# 1-Schematic_Logic.net
KiCad netlist of a schematic drawn in EasyEDA
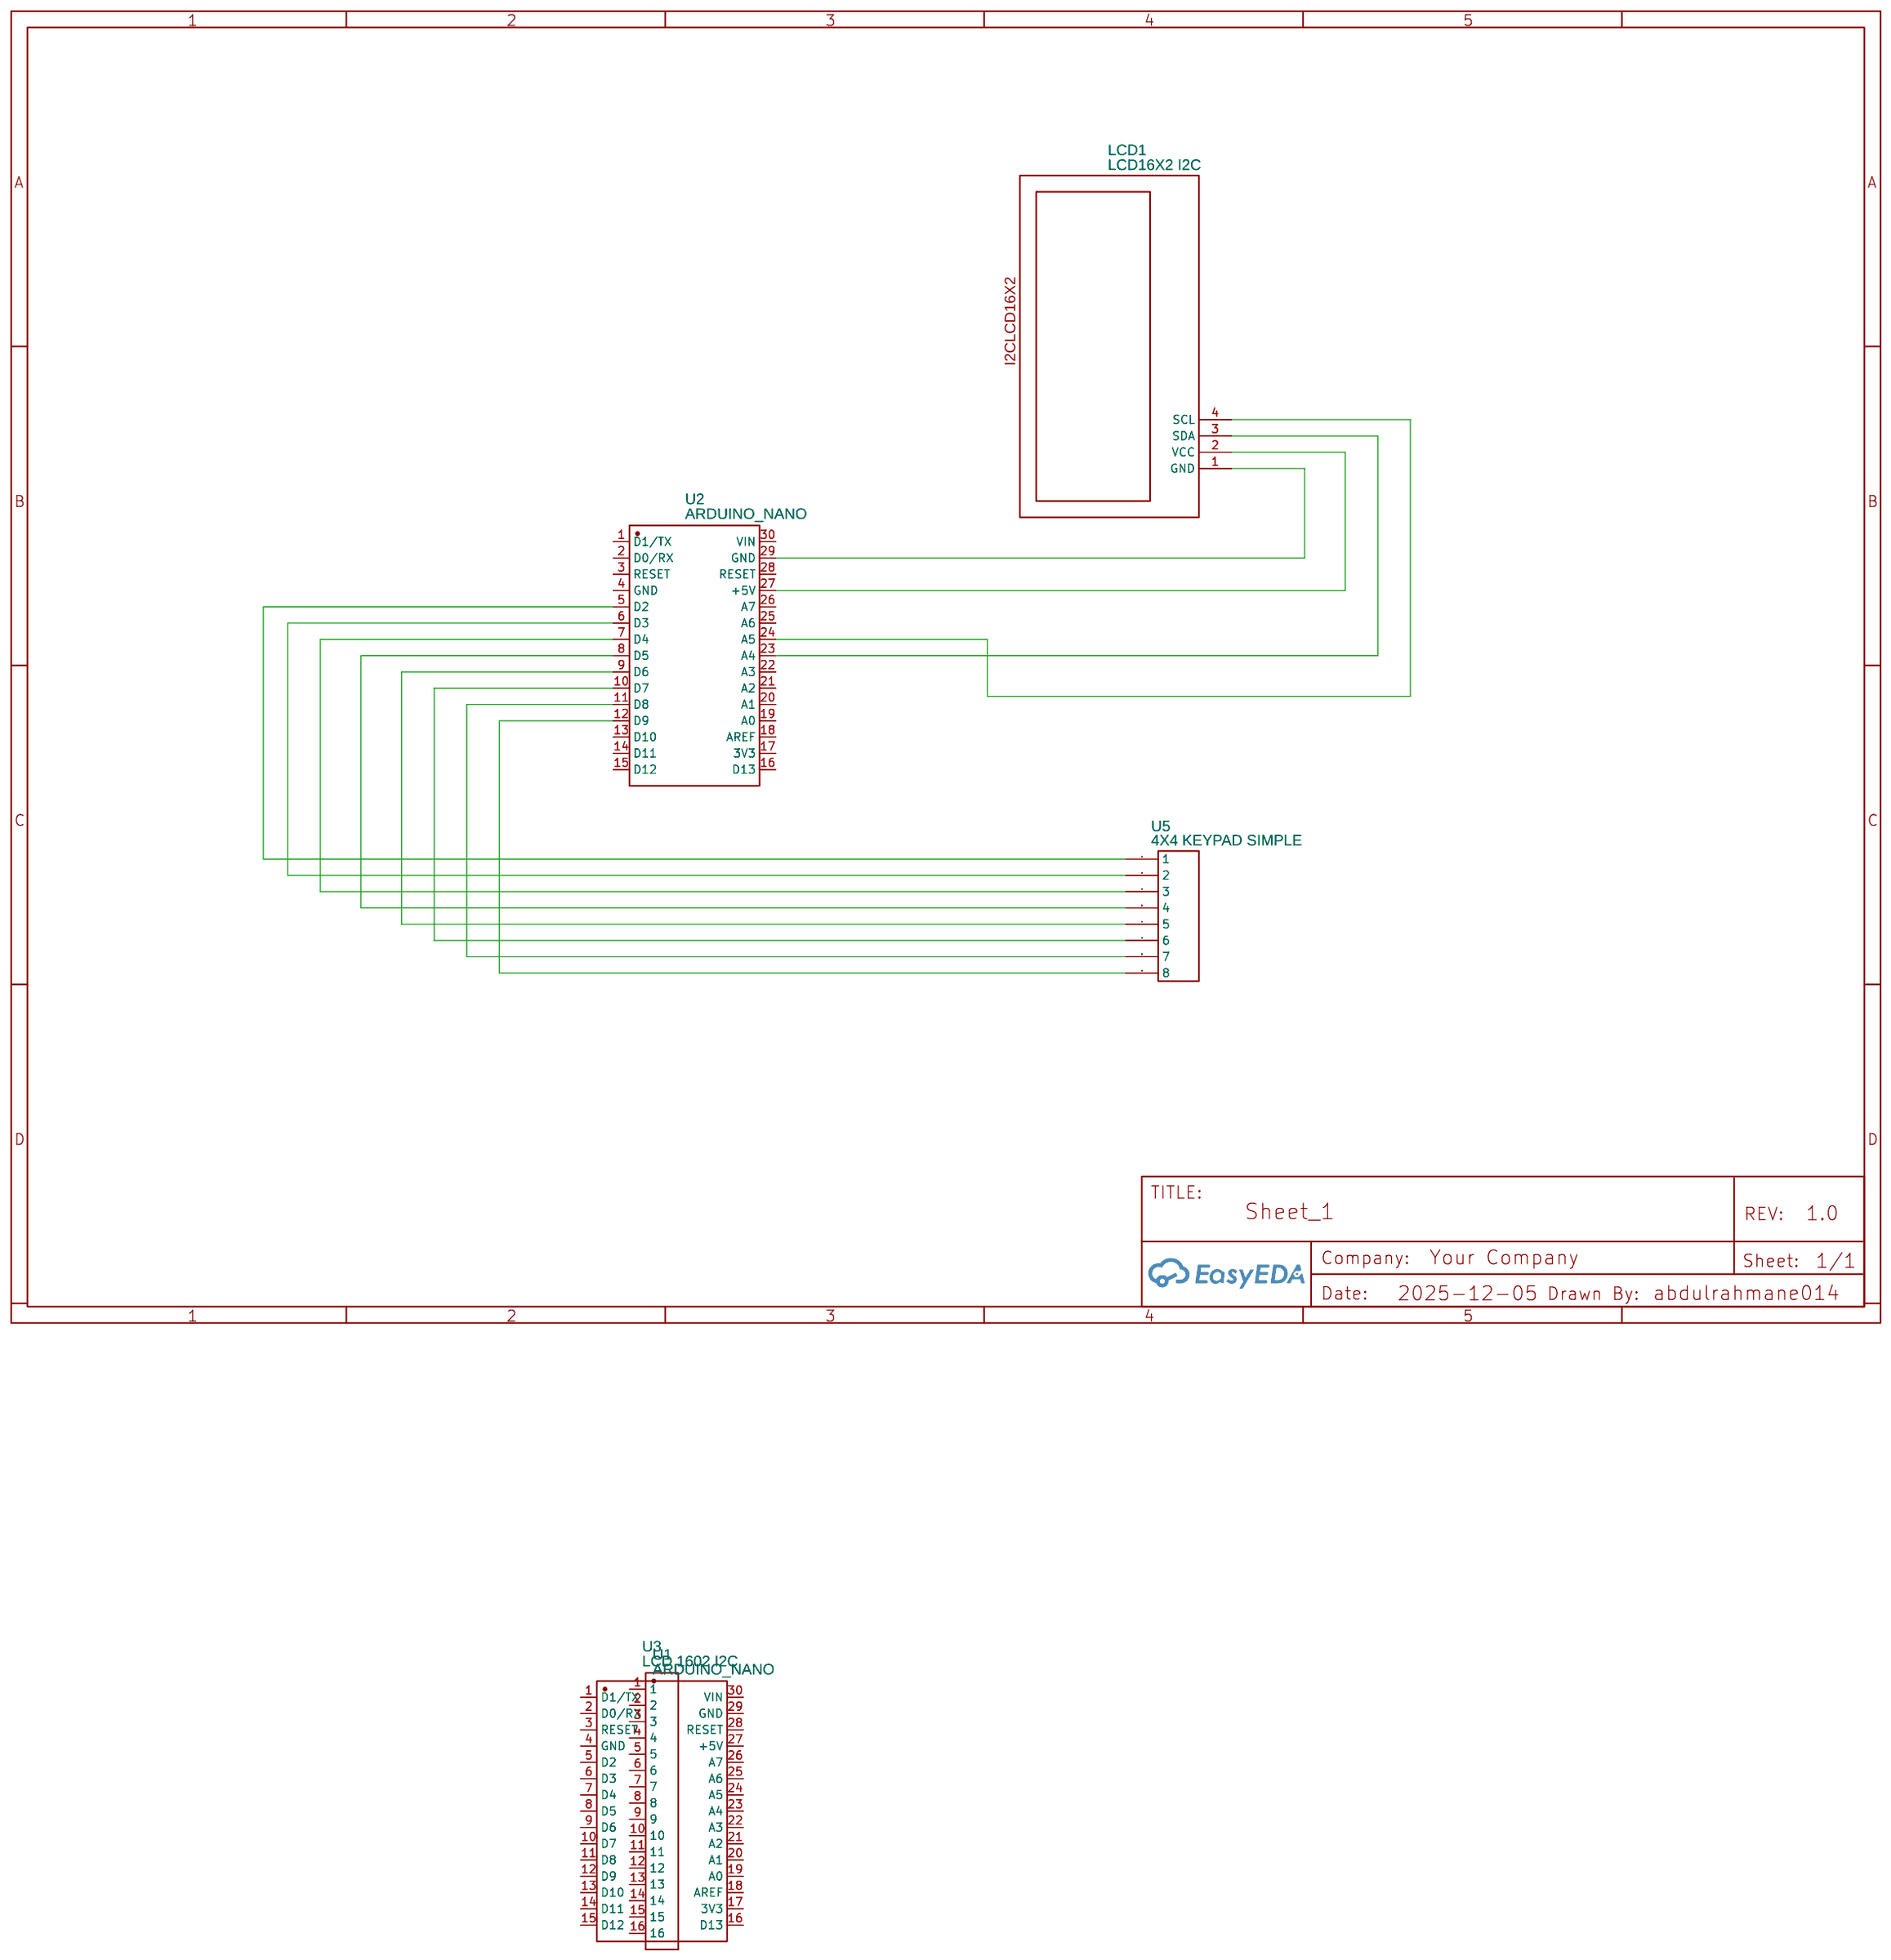
[diagram p0: schematic sheet]

(export (version "E")
  (design (tool "Eeschema 10.0.6"))
  (components
    (comp (ref "LCD1") (value "LCD16X2 I2C") (libsource (lib "") (part "LCD16X2 I2C")))
    (comp (ref "U1") (value "ARDUINO_NANO") (libsource (lib "") (part "ARDUINO_NANO")))
    (comp (ref "U2") (value "ARDUINO_NANO") (libsource (lib "") (part "ARDUINO_NANO")))
    (comp (ref "U3") (value "LCD 1602 I2C") (libsource (lib "") (part "LCD 1602 I2C")))
    (comp (ref "U5") (value "4X4 KEYPAD SIMPLE") (libsource (lib "") (part "4X4 KEYPAD SIMPLE")))
  )
  (nets
    (net (code "1") (name "Net-(LCD1-GND)") (class "Default")
      (node (ref "LCD1") (pin "1") (pinfunction "GND_1") (pintype "unspecified"))
      (node (ref "U2") (pin "29") (pinfunction "GND_29") (pintype "unspecified"))
    )
    (net (code "2") (name "Net-(LCD1-SCL)") (class "Default")
      (node (ref "LCD1") (pin "4") (pinfunction "SCL_4") (pintype "unspecified"))
      (node (ref "U2") (pin "24") (pinfunction "A5_24") (pintype "unspecified"))
    )
    (net (code "3") (name "Net-(LCD1-SDA)") (class "Default")
      (node (ref "LCD1") (pin "3") (pinfunction "SDA_3") (pintype "unspecified"))
      (node (ref "U2") (pin "23") (pinfunction "A4_23") (pintype "unspecified"))
    )
    (net (code "4") (name "Net-(LCD1-VCC)") (class "Default")
      (node (ref "LCD1") (pin "2") (pinfunction "VCC_2") (pintype "unspecified"))
      (node (ref "U2") (pin "27") (pinfunction "+5V_27") (pintype "unspecified"))
    )
    (net (code "5") (name "Net-(U2-D2)") (class "Default")
      (node (ref "U2") (pin "5") (pinfunction "D2_5") (pintype "unspecified"))
      (node (ref "U5") (pin "3") (pinfunction "1_3") (pintype "unspecified"))
    )
    (net (code "6") (name "Net-(U2-D3)") (class "Default")
      (node (ref "U2") (pin "6") (pinfunction "D3_6") (pintype "unspecified"))
      (node (ref "U5") (pin "4") (pinfunction "2_4") (pintype "unspecified"))
    )
    (net (code "7") (name "Net-(U2-D4)") (class "Default")
      (node (ref "U2") (pin "7") (pinfunction "D4_7") (pintype "unspecified"))
      (node (ref "U5") (pin "5") (pinfunction "3_5") (pintype "unspecified"))
    )
    (net (code "8") (name "Net-(U2-D5)") (class "Default")
      (node (ref "U2") (pin "8") (pinfunction "D5_8") (pintype "unspecified"))
      (node (ref "U5") (pin "6") (pinfunction "4_6") (pintype "unspecified"))
    )
    (net (code "9") (name "Net-(U2-D6)") (class "Default")
      (node (ref "U2") (pin "9") (pinfunction "D6_9") (pintype "unspecified"))
      (node (ref "U5") (pin "7") (pinfunction "5_7") (pintype "unspecified"))
    )
    (net (code "10") (name "Net-(U2-D7)") (class "Default")
      (node (ref "U2") (pin "10") (pinfunction "D7_10") (pintype "unspecified"))
      (node (ref "U5") (pin "8") (pinfunction "6_8") (pintype "unspecified"))
    )
    (net (code "11") (name "Net-(U2-D8)") (class "Default")
      (node (ref "U2") (pin "11") (pinfunction "D8_11") (pintype "unspecified"))
      (node (ref "U5") (pin "9") (pinfunction "7_9") (pintype "unspecified"))
    )
    (net (code "12") (name "Net-(U2-D9)") (class "Default")
      (node (ref "U2") (pin "12") (pinfunction "D9_12") (pintype "unspecified"))
      (node (ref "U5") (pin "10") (pinfunction "8_10") (pintype "unspecified"))
    )
    (net (code "13") (name "unconnected-(U1-+5V-Pad27)") (class "Default")
      (node (ref "U1") (pin "27") (pinfunction "+5V_27") (pintype "unspecified"))
    )
    (net (code "14") (name "unconnected-(U1-3V3-Pad17)") (class "Default")
      (node (ref "U1") (pin "17") (pinfunction "3V3_17") (pintype "unspecified"))
    )
    (net (code "15") (name "unconnected-(U1-A0-Pad19)") (class "Default")
      (node (ref "U1") (pin "19") (pinfunction "A0_19") (pintype "unspecified"))
    )
    (net (code "16") (name "unconnected-(U1-A1-Pad20)") (class "Default")
      (node (ref "U1") (pin "20") (pinfunction "A1_20") (pintype "unspecified"))
    )
    (net (code "17") (name "unconnected-(U1-A2-Pad21)") (class "Default")
      (node (ref "U1") (pin "21") (pinfunction "A2_21") (pintype "unspecified"))
    )
    (net (code "18") (name "unconnected-(U1-A3-Pad22)") (class "Default")
      (node (ref "U1") (pin "22") (pinfunction "A3_22") (pintype "unspecified"))
    )
    (net (code "19") (name "unconnected-(U1-A4-Pad23)") (class "Default")
      (node (ref "U1") (pin "23") (pinfunction "A4_23") (pintype "unspecified"))
    )
    (net (code "20") (name "unconnected-(U1-A5-Pad24)") (class "Default")
      (node (ref "U1") (pin "24") (pinfunction "A5_24") (pintype "unspecified"))
    )
    (net (code "21") (name "unconnected-(U1-A6-Pad25)") (class "Default")
      (node (ref "U1") (pin "25") (pinfunction "A6_25") (pintype "unspecified"))
    )
    (net (code "22") (name "unconnected-(U1-A7-Pad26)") (class "Default")
      (node (ref "U1") (pin "26") (pinfunction "A7_26") (pintype "unspecified"))
    )
    (net (code "23") (name "unconnected-(U1-AREF-Pad18)") (class "Default")
      (node (ref "U1") (pin "18") (pinfunction "AREF_18") (pintype "unspecified"))
    )
    (net (code "24") (name "unconnected-(U1-D0{slash}RX-Pad2)") (class "Default")
      (node (ref "U1") (pin "2") (pinfunction "D0/RX_2") (pintype "unspecified"))
    )
    (net (code "25") (name "unconnected-(U1-D1{slash}TX-Pad1)") (class "Default")
      (node (ref "U1") (pin "1") (pinfunction "D1/TX_1") (pintype "unspecified"))
    )
    (net (code "26") (name "unconnected-(U1-D2-Pad5)") (class "Default")
      (node (ref "U1") (pin "5") (pinfunction "D2_5") (pintype "unspecified"))
    )
    (net (code "27") (name "unconnected-(U1-D3-Pad6)") (class "Default")
      (node (ref "U1") (pin "6") (pinfunction "D3_6") (pintype "unspecified"))
    )
    (net (code "28") (name "unconnected-(U1-D4-Pad7)") (class "Default")
      (node (ref "U1") (pin "7") (pinfunction "D4_7") (pintype "unspecified"))
    )
    (net (code "29") (name "unconnected-(U1-D5-Pad8)") (class "Default")
      (node (ref "U1") (pin "8") (pinfunction "D5_8") (pintype "unspecified"))
    )
    (net (code "30") (name "unconnected-(U1-D6-Pad9)") (class "Default")
      (node (ref "U1") (pin "9") (pinfunction "D6_9") (pintype "unspecified"))
    )
    (net (code "31") (name "unconnected-(U1-D7-Pad10)") (class "Default")
      (node (ref "U1") (pin "10") (pinfunction "D7_10") (pintype "unspecified"))
    )
    (net (code "32") (name "unconnected-(U1-D8-Pad11)") (class "Default")
      (node (ref "U1") (pin "11") (pinfunction "D8_11") (pintype "unspecified"))
    )
    (net (code "33") (name "unconnected-(U1-D9-Pad12)") (class "Default")
      (node (ref "U1") (pin "12") (pinfunction "D9_12") (pintype "unspecified"))
    )
    (net (code "34") (name "unconnected-(U1-D10-Pad13)") (class "Default")
      (node (ref "U1") (pin "13") (pinfunction "D10_13") (pintype "unspecified"))
    )
    (net (code "35") (name "unconnected-(U1-D11-Pad14)") (class "Default")
      (node (ref "U1") (pin "14") (pinfunction "D11_14") (pintype "unspecified"))
    )
    (net (code "36") (name "unconnected-(U1-D12-Pad15)") (class "Default")
      (node (ref "U1") (pin "15") (pinfunction "D12_15") (pintype "unspecified"))
    )
    (net (code "37") (name "unconnected-(U1-D13-Pad16)") (class "Default")
      (node (ref "U1") (pin "16") (pinfunction "D13_16") (pintype "unspecified"))
    )
    (net (code "38") (name "unconnected-(U1-GND-Pad4)") (class "Default")
      (node (ref "U1") (pin "4") (pinfunction "GND_4") (pintype "unspecified"))
    )
    (net (code "39") (name "unconnected-(U1-GND-Pad29)") (class "Default")
      (node (ref "U1") (pin "29") (pinfunction "GND_29") (pintype "unspecified"))
    )
    (net (code "40") (name "unconnected-(U1-RESET-Pad3)") (class "Default")
      (node (ref "U1") (pin "3") (pinfunction "RESET_3") (pintype "unspecified"))
    )
    (net (code "41") (name "unconnected-(U1-RESET-Pad28)") (class "Default")
      (node (ref "U1") (pin "28") (pinfunction "RESET_28") (pintype "unspecified"))
    )
    (net (code "42") (name "unconnected-(U1-VIN-Pad30)") (class "Default")
      (node (ref "U1") (pin "30") (pinfunction "VIN_30") (pintype "unspecified"))
    )
    (net (code "43") (name "unconnected-(U2-3V3-Pad17)") (class "Default")
      (node (ref "U2") (pin "17") (pinfunction "3V3_17") (pintype "unspecified"))
    )
    (net (code "44") (name "unconnected-(U2-A0-Pad19)") (class "Default")
      (node (ref "U2") (pin "19") (pinfunction "A0_19") (pintype "unspecified"))
    )
    (net (code "45") (name "unconnected-(U2-A1-Pad20)") (class "Default")
      (node (ref "U2") (pin "20") (pinfunction "A1_20") (pintype "unspecified"))
    )
    (net (code "46") (name "unconnected-(U2-A2-Pad21)") (class "Default")
      (node (ref "U2") (pin "21") (pinfunction "A2_21") (pintype "unspecified"))
    )
    (net (code "47") (name "unconnected-(U2-A3-Pad22)") (class "Default")
      (node (ref "U2") (pin "22") (pinfunction "A3_22") (pintype "unspecified"))
    )
    (net (code "48") (name "unconnected-(U2-A6-Pad25)") (class "Default")
      (node (ref "U2") (pin "25") (pinfunction "A6_25") (pintype "unspecified"))
    )
    (net (code "49") (name "unconnected-(U2-A7-Pad26)") (class "Default")
      (node (ref "U2") (pin "26") (pinfunction "A7_26") (pintype "unspecified"))
    )
    (net (code "50") (name "unconnected-(U2-AREF-Pad18)") (class "Default")
      (node (ref "U2") (pin "18") (pinfunction "AREF_18") (pintype "unspecified"))
    )
    (net (code "51") (name "unconnected-(U2-D0{slash}RX-Pad2)") (class "Default")
      (node (ref "U2") (pin "2") (pinfunction "D0/RX_2") (pintype "unspecified"))
    )
    (net (code "52") (name "unconnected-(U2-D1{slash}TX-Pad1)") (class "Default")
      (node (ref "U2") (pin "1") (pinfunction "D1/TX_1") (pintype "unspecified"))
    )
    (net (code "53") (name "unconnected-(U2-D10-Pad13)") (class "Default")
      (node (ref "U2") (pin "13") (pinfunction "D10_13") (pintype "unspecified"))
    )
    (net (code "54") (name "unconnected-(U2-D11-Pad14)") (class "Default")
      (node (ref "U2") (pin "14") (pinfunction "D11_14") (pintype "unspecified"))
    )
    (net (code "55") (name "unconnected-(U2-D12-Pad15)") (class "Default")
      (node (ref "U2") (pin "15") (pinfunction "D12_15") (pintype "unspecified"))
    )
    (net (code "56") (name "unconnected-(U2-D13-Pad16)") (class "Default")
      (node (ref "U2") (pin "16") (pinfunction "D13_16") (pintype "unspecified"))
    )
    (net (code "57") (name "unconnected-(U2-GND-Pad4)") (class "Default")
      (node (ref "U2") (pin "4") (pinfunction "GND_4") (pintype "unspecified"))
    )
    (net (code "58") (name "unconnected-(U2-RESET-Pad3)") (class "Default")
      (node (ref "U2") (pin "3") (pinfunction "RESET_3") (pintype "unspecified"))
    )
    (net (code "59") (name "unconnected-(U2-RESET-Pad28)") (class "Default")
      (node (ref "U2") (pin "28") (pinfunction "RESET_28") (pintype "unspecified"))
    )
    (net (code "60") (name "unconnected-(U2-VIN-Pad30)") (class "Default")
      (node (ref "U2") (pin "30") (pinfunction "VIN_30") (pintype "unspecified"))
    )
    (net (code "61") (name "unconnected-(U3-Pad1)") (class "Default")
      (node (ref "U3") (pin "1") (pinfunction "1_1") (pintype "unspecified"))
    )
    (net (code "62") (name "unconnected-(U3-Pad2)") (class "Default")
      (node (ref "U3") (pin "2") (pinfunction "2_2") (pintype "unspecified"))
    )
    (net (code "63") (name "unconnected-(U3-Pad3)") (class "Default")
      (node (ref "U3") (pin "3") (pinfunction "3_3") (pintype "unspecified"))
    )
    (net (code "64") (name "unconnected-(U3-Pad4)") (class "Default")
      (node (ref "U3") (pin "4") (pinfunction "4_4") (pintype "unspecified"))
    )
    (net (code "65") (name "unconnected-(U3-Pad5)") (class "Default")
      (node (ref "U3") (pin "5") (pinfunction "5_5") (pintype "unspecified"))
    )
    (net (code "66") (name "unconnected-(U3-Pad6)") (class "Default")
      (node (ref "U3") (pin "6") (pinfunction "6_6") (pintype "unspecified"))
    )
    (net (code "67") (name "unconnected-(U3-Pad7)") (class "Default")
      (node (ref "U3") (pin "7") (pinfunction "7_7") (pintype "unspecified"))
    )
    (net (code "68") (name "unconnected-(U3-Pad8)") (class "Default")
      (node (ref "U3") (pin "8") (pinfunction "8_8") (pintype "unspecified"))
    )
    (net (code "69") (name "unconnected-(U3-Pad9)") (class "Default")
      (node (ref "U3") (pin "9") (pinfunction "9_9") (pintype "unspecified"))
    )
    (net (code "70") (name "unconnected-(U3-Pad10)") (class "Default")
      (node (ref "U3") (pin "10") (pinfunction "10_10") (pintype "unspecified"))
    )
    (net (code "71") (name "unconnected-(U3-Pad11)") (class "Default")
      (node (ref "U3") (pin "11") (pinfunction "11_11") (pintype "unspecified"))
    )
    (net (code "72") (name "unconnected-(U3-Pad12)") (class "Default")
      (node (ref "U3") (pin "12") (pinfunction "12_12") (pintype "unspecified"))
    )
    (net (code "73") (name "unconnected-(U3-Pad13)") (class "Default")
      (node (ref "U3") (pin "13") (pinfunction "13_13") (pintype "unspecified"))
    )
    (net (code "74") (name "unconnected-(U3-Pad14)") (class "Default")
      (node (ref "U3") (pin "14") (pinfunction "14_14") (pintype "unspecified"))
    )
    (net (code "75") (name "unconnected-(U3-Pad15)") (class "Default")
      (node (ref "U3") (pin "15") (pinfunction "15_15") (pintype "unspecified"))
    )
    (net (code "76") (name "unconnected-(U3-Pad16)") (class "Default")
      (node (ref "U3") (pin "16") (pinfunction "16_16") (pintype "unspecified"))
    )
  )
)
